# Interface.net
KiCad netlist of a schematic drawn in EAGLE
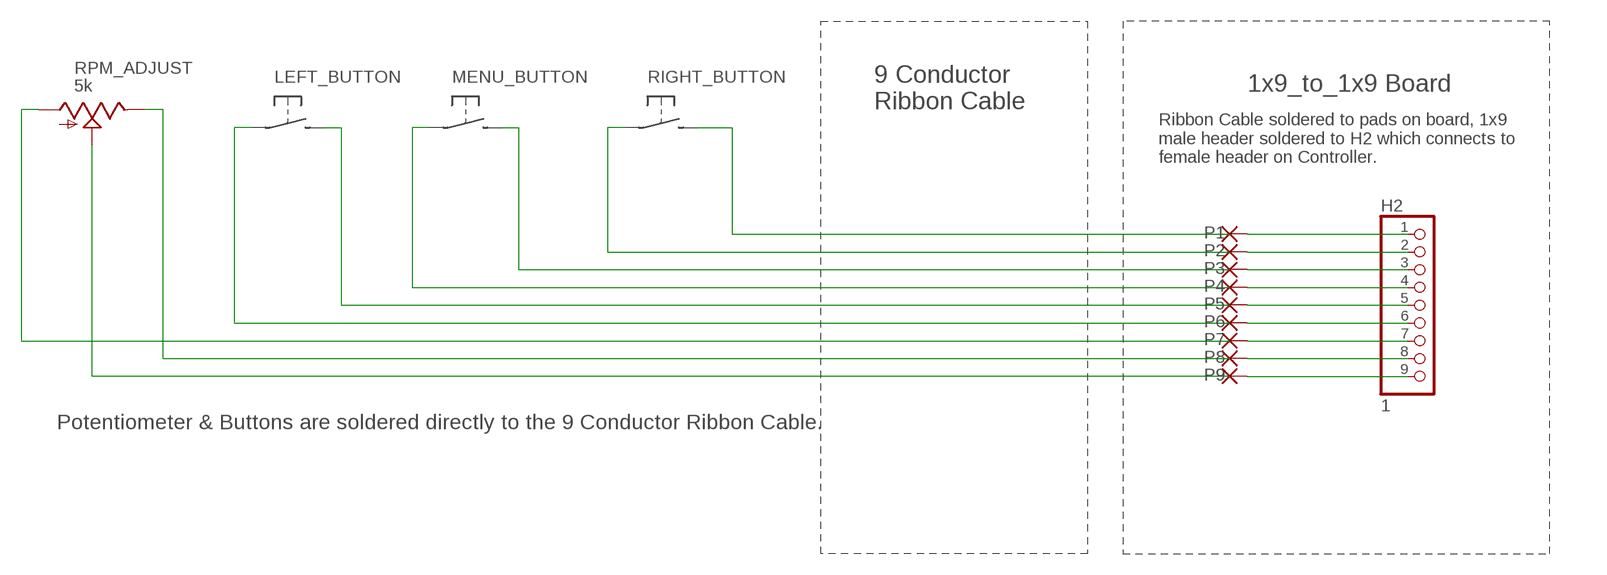
[diagram p0: schematic, sheet 1]

(export (version "E")
  (design (tool "Eeschema 10.0.6"))
  (components
    (comp (ref "H2")
      (value "1")
      (footprint "eagle-import:1X09")
      (libsource (lib "eagle-import") (part "PINHD-1X9"))
    )
    (comp (ref "P1")
      (value "1,6/0,9")
      (footprint "eagle-import:1,6_0,9")
      (libsource (lib "eagle-import") (part "1,6/0,9"))
    )
    (comp (ref "P2")
      (value "1,6/0,9")
      (footprint "eagle-import:1,6_0,9")
      (libsource (lib "eagle-import") (part "1,6/0,9"))
    )
    (comp (ref "P3")
      (value "1,6/0,9")
      (footprint "eagle-import:1,6_0,9")
      (libsource (lib "eagle-import") (part "1,6/0,9"))
    )
    (comp (ref "P4")
      (value "1,6/0,9")
      (footprint "eagle-import:1,6_0,9")
      (libsource (lib "eagle-import") (part "1,6/0,9"))
    )
    (comp (ref "P5")
      (value "1,6/0,9")
      (footprint "eagle-import:1,6_0,9")
      (libsource (lib "eagle-import") (part "1,6/0,9"))
    )
    (comp (ref "P6")
      (value "1,6/0,9")
      (footprint "eagle-import:1,6_0,9")
      (libsource (lib "eagle-import") (part "1,6/0,9"))
    )
    (comp (ref "P7")
      (value "1,6/0,9")
      (footprint "eagle-import:1,6_0,9")
      (libsource (lib "eagle-import") (part "1,6/0,9"))
    )
    (comp (ref "P8")
      (value "1,6/0,9")
      (footprint "eagle-import:1,6_0,9")
      (libsource (lib "eagle-import") (part "1,6/0,9"))
    )
    (comp (ref "P9")
      (value "1,6/0,9")
      (footprint "eagle-import:1,6_0,9")
      (libsource (lib "eagle-import") (part "1,6/0,9"))
    )
    (comp (ref "RPM_ADJUST")
      (value "5k")
      (footprint "eagle-import:CIP20C-6MM")
      (libsource (lib "eagle-import") (part "TRIM_US-CIP20C-6MM"))
    )
  )
  (nets
    (net (code "1") (name "Net-(P1-P)") (class "Default")
      (node (ref "H2") (pin "1") (pinfunction "1_1") (pintype "passive"))
      (node (ref "P1") (pin "1") (pinfunction "P_1") (pintype "passive"))
    )
    (net (code "2") (name "Net-(P2-P)") (class "Default")
      (node (ref "H2") (pin "2") (pinfunction "2_2") (pintype "passive"))
      (node (ref "P2") (pin "1") (pinfunction "P_1") (pintype "passive"))
    )
    (net (code "3") (name "Net-(P3-P)") (class "Default")
      (node (ref "H2") (pin "3") (pinfunction "3_3") (pintype "passive"))
      (node (ref "P3") (pin "1") (pinfunction "P_1") (pintype "passive"))
    )
    (net (code "4") (name "Net-(P4-P)") (class "Default")
      (node (ref "H2") (pin "4") (pinfunction "4_4") (pintype "passive"))
      (node (ref "P4") (pin "1") (pinfunction "P_1") (pintype "passive"))
    )
    (net (code "5") (name "Net-(P5-P)") (class "Default")
      (node (ref "H2") (pin "5") (pinfunction "5_5") (pintype "passive"))
      (node (ref "P5") (pin "1") (pinfunction "P_1") (pintype "passive"))
    )
    (net (code "6") (name "Net-(P6-P)") (class "Default")
      (node (ref "H2") (pin "6") (pinfunction "6_6") (pintype "passive"))
      (node (ref "P6") (pin "1") (pinfunction "P_1") (pintype "passive"))
    )
    (net (code "7") (name "Net-(P7-P)") (class "Default")
      (node (ref "H2") (pin "7") (pinfunction "7_7") (pintype "passive"))
      (node (ref "P7") (pin "1") (pinfunction "P_1") (pintype "passive"))
    )
    (net (code "8") (name "Net-(P8-P)") (class "Default")
      (node (ref "H2") (pin "8") (pinfunction "8_8") (pintype "passive"))
      (node (ref "P8") (pin "1") (pinfunction "P_1") (pintype "passive"))
    )
    (net (code "9") (name "Net-(P9-P)") (class "Default")
      (node (ref "H2") (pin "9") (pinfunction "9_9") (pintype "passive"))
      (node (ref "P9") (pin "1") (pinfunction "P_1") (pintype "passive"))
    )
    (net (code "10") (name "unconnected-(RPM_ADJUST-PadA)") (class "Default")
      (node (ref "RPM_ADJUST") (pin "A") (pinfunction "A_A") (pintype "passive"))
    )
    (net (code "11") (name "unconnected-(RPM_ADJUST-PadE)") (class "Default")
      (node (ref "RPM_ADJUST") (pin "E") (pinfunction "E_E") (pintype "passive"))
    )
    (net (code "12") (name "unconnected-(RPM_ADJUST-PadS)") (class "Default")
      (node (ref "RPM_ADJUST") (pin "S") (pinfunction "S_S") (pintype "passive"))
    )
  )
)
